# rascsi_din.net
KiCad netlist of a schematic drawn in EAGLE
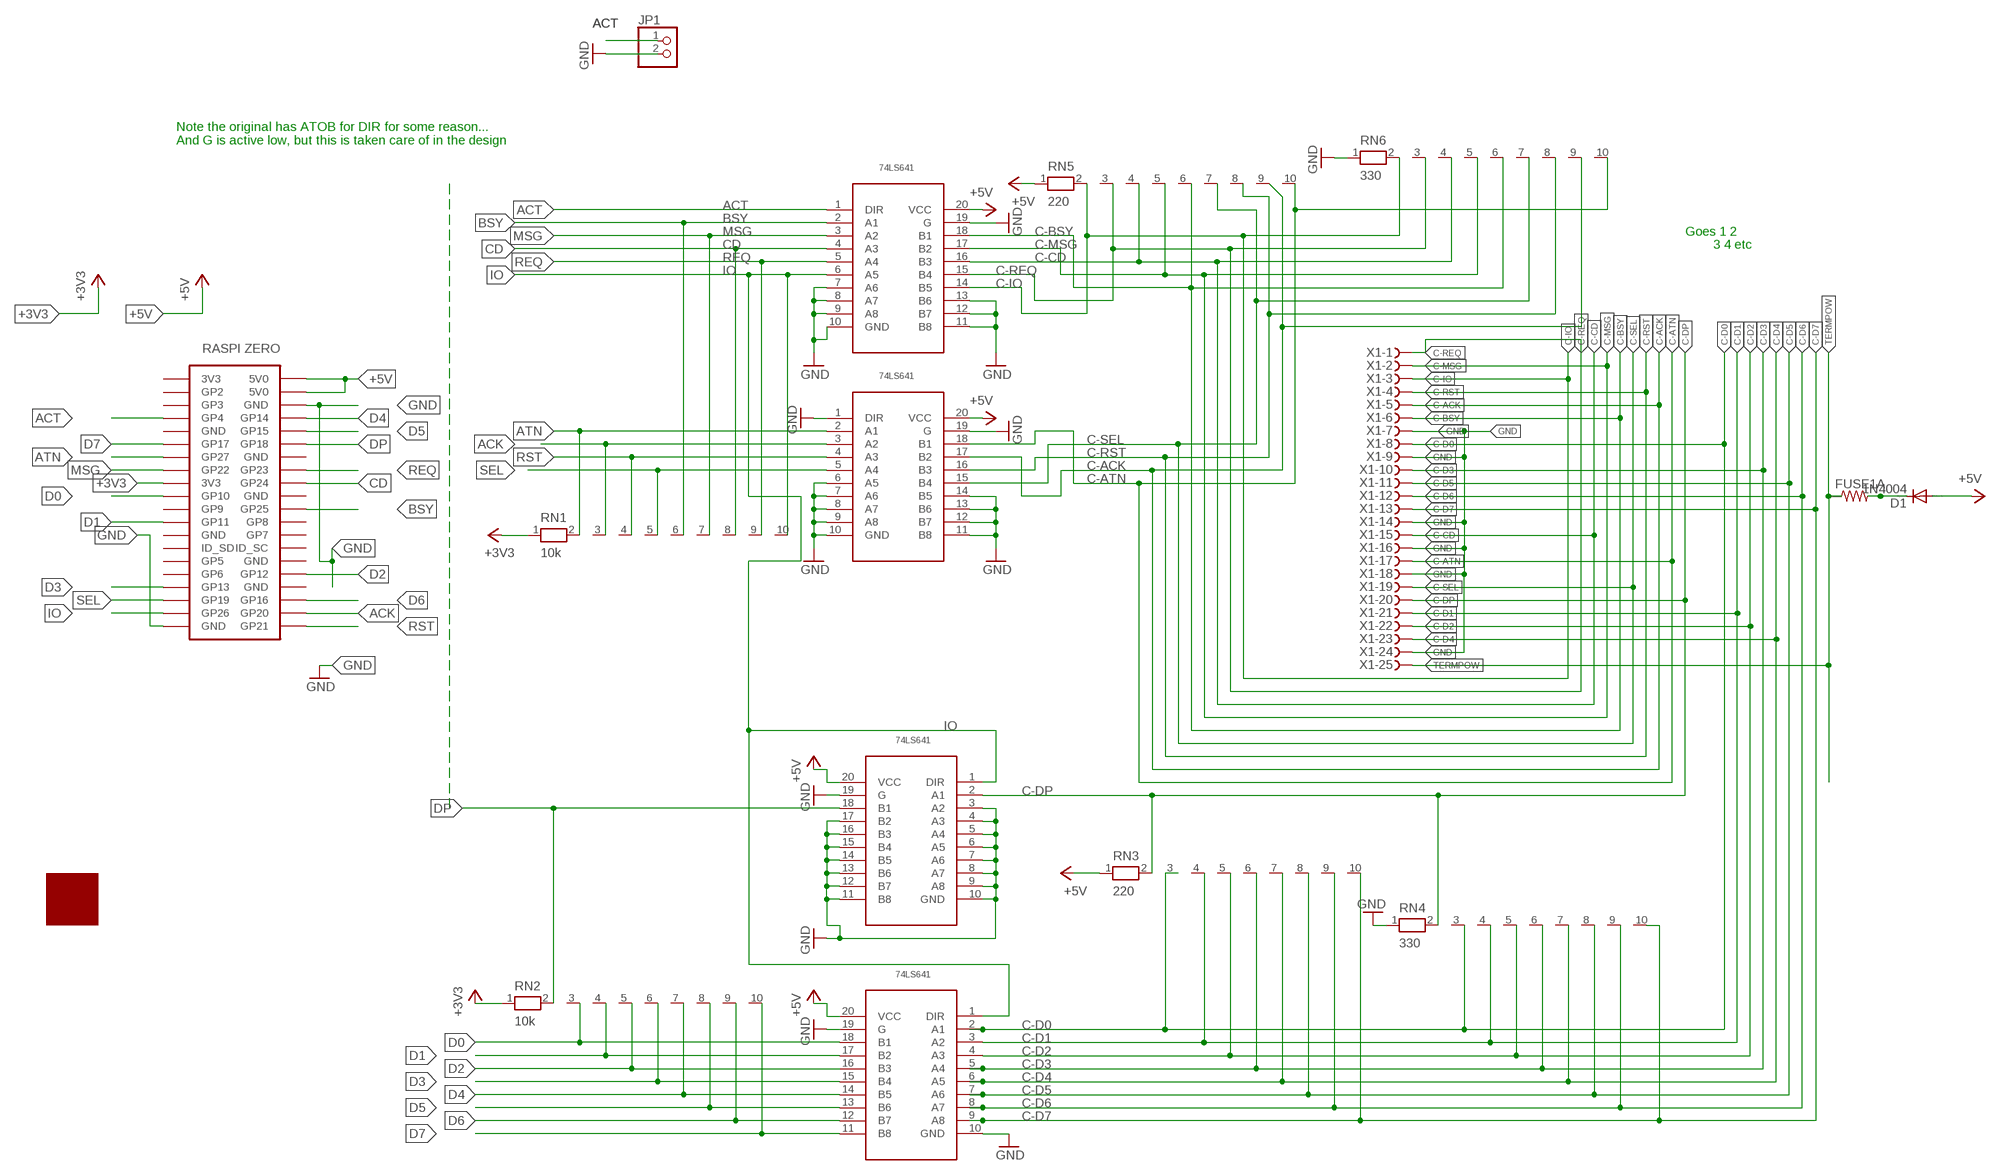
[diagram p0: schematic, sheet 1]

(export (version "E")
  (design (tool "Eeschema 10.0.6"))
  (components
    (comp (ref "D1")
      (value "1N4004")
      (footprint "eagle-import:DO41-10")
      (libsource (lib "eagle-import") (part "1N4004"))
    )
    (comp (ref "FUSE1A")
      (value "R-US_0204/7")
      (footprint "eagle-import:0204_7")
      (libsource (lib "eagle-import") (part "R-US_0204/7"))
    )
    (comp (ref "JP1")
      (value "PINHD-1X2")
      (footprint "eagle-import:1X02")
      (libsource (lib "eagle-import") (part "PINHD-1X2"))
    )
    (comp (ref "RN1")
      (value "10k")
      (footprint "eagle-import:RN-10")
      (libsource (lib "eagle-import") (part "RN09"))
    )
    (comp (ref "RN2")
      (value "10k")
      (footprint "eagle-import:RN-10")
      (libsource (lib "eagle-import") (part "RN09"))
    )
    (comp (ref "RN3")
      (value "220")
      (footprint "eagle-import:RN-10")
      (libsource (lib "eagle-import") (part "RN09"))
    )
    (comp (ref "RN4")
      (value "330")
      (footprint "eagle-import:RN-10")
      (libsource (lib "eagle-import") (part "RN09"))
    )
    (comp (ref "RN5")
      (value "220")
      (footprint "eagle-import:RN-10")
      (libsource (lib "eagle-import") (part "RN09"))
    )
    (comp (ref "RN6")
      (value "330")
      (footprint "eagle-import:RN-10")
      (libsource (lib "eagle-import") (part "RN09"))
    )
    (comp (ref "U$1")
      (value "ZERO")
      (footprint "eagle-import:ZERO")
      (libsource (lib "eagle-import") (part "ZERO"))
    )
    (comp (ref "U$2")
      (value "LOGO")
      (footprint "eagle-import:LOGO")
      (libsource (lib "eagle-import") (part "LOGO"))
    )
    (comp (ref "U11")
      (value "SN74LS641-1SC")
      (footprint "eagle-import:SOIC20S")
      (libsource (lib "eagle-import") (part "SN74LS641-1CS"))
    )
    (comp (ref "U22")
      (value "SN74LS641-1SC")
      (footprint "eagle-import:SOIC20S")
      (libsource (lib "eagle-import") (part "SN74LS641-1CS"))
    )
    (comp (ref "U33")
      (value "SN74LS641-1SC")
      (footprint "eagle-import:SOIC20S")
      (libsource (lib "eagle-import") (part "SN74LS641-1CS"))
    )
    (comp (ref "U44")
      (value "SN74LS641-1SC")
      (footprint "eagle-import:SOIC20S")
      (libsource (lib "eagle-import") (part "SN74LS641-1CS"))
    )
    (comp (ref "X1")
      (value "F25HPS")
      (footprint "eagle-import:F25HP")
      (libsource (lib "eagle-import") (part "F25?SHP"))
    )
  )
  (nets
    (net (code "1") (name "+3V3") (class "Default")
      (node (ref "RN1") (pin "1") (pinfunction "1_1") (pintype "passive"))
      (node (ref "RN2") (pin "1") (pinfunction "1_1") (pintype "passive"))
      (node (ref "U$1") (pin "17") (pinfunction "3V3_17") (pintype "bidirectional"))
    )
    (net (code "2") (name "+5V") (class "Default")
      (node (ref "D1") (pin "A") (pinfunction "A_A") (pintype "passive"))
      (node (ref "RN3") (pin "1") (pinfunction "1_1") (pintype "passive"))
      (node (ref "RN5") (pin "1") (pinfunction "1_1") (pintype "passive"))
      (node (ref "U$1") (pin "2") (pinfunction "5V0_2") (pintype "bidirectional"))
      (node (ref "U$1") (pin "4") (pinfunction "5V0_4") (pintype "bidirectional"))
      (node (ref "U11") (pin "20") (pinfunction "VCC_20") (pintype "power_in"))
      (node (ref "U22") (pin "20") (pinfunction "VCC_20") (pintype "power_in"))
      (node (ref "U33") (pin "20") (pinfunction "VCC_20") (pintype "power_in"))
      (node (ref "U44") (pin "20") (pinfunction "VCC_20") (pintype "power_in"))
    )
    (net (code "3") (name "ACK") (class "Default")
      (node (ref "RN1") (pin "3") (pinfunction "3_3") (pintype "passive"))
      (node (ref "U$1") (pin "38") (pinfunction "GP20_38") (pintype "bidirectional"))
      (node (ref "U22") (pin "3") (pinfunction "A2_3") (pintype "bidirectional"))
    )
    (net (code "4") (name "ACT") (class "Default")
      (node (ref "JP1") (pin "1") (pinfunction "1_1") (pintype "passive"))
      (node (ref "U$1") (pin "7") (pinfunction "GP4_7") (pintype "bidirectional"))
      (node (ref "U11") (pin "1") (pinfunction "DIR_1") (pintype "bidirectional"))
    )
    (net (code "5") (name "ATN") (class "Default")
      (node (ref "RN1") (pin "2") (pinfunction "2_2") (pintype "passive"))
      (node (ref "U$1") (pin "13") (pinfunction "GP27_13") (pintype "bidirectional"))
      (node (ref "U22") (pin "2") (pinfunction "A1_2") (pintype "bidirectional"))
    )
    (net (code "6") (name "BSY") (class "Default")
      (node (ref "RN1") (pin "6") (pinfunction "6_6") (pintype "passive"))
      (node (ref "U$1") (pin "22") (pinfunction "GP25_22") (pintype "bidirectional"))
      (node (ref "U11") (pin "2") (pinfunction "A1_2") (pintype "bidirectional"))
    )
    (net (code "7") (name "C-ACK") (class "Default")
      (node (ref "RN5") (pin "9") (pinfunction "9_9") (pintype "passive"))
      (node (ref "RN6") (pin "9") (pinfunction "9_9") (pintype "passive"))
      (node (ref "U22") (pin "17") (pinfunction "B2_17") (pintype "bidirectional"))
      (node (ref "X1") (pin "5") (pinfunction "F_5") (pintype "passive"))
    )
    (net (code "8") (name "C-ATN") (class "Default")
      (node (ref "RN5") (pin "10") (pinfunction "10_10") (pintype "passive"))
      (node (ref "RN6") (pin "10") (pinfunction "10_10") (pintype "passive"))
      (node (ref "U22") (pin "18") (pinfunction "B1_18") (pintype "bidirectional"))
      (node (ref "X1") (pin "17") (pinfunction "F_17") (pintype "passive"))
    )
    (net (code "9") (name "C-BSY") (class "Default")
      (node (ref "RN5") (pin "6") (pinfunction "6_6") (pintype "passive"))
      (node (ref "RN6") (pin "6") (pinfunction "6_6") (pintype "passive"))
      (node (ref "U11") (pin "18") (pinfunction "B1_18") (pintype "bidirectional"))
      (node (ref "X1") (pin "6") (pinfunction "F_6") (pintype "passive"))
    )
    (net (code "10") (name "C-CD") (class "Default")
      (node (ref "RN5") (pin "4") (pinfunction "4_4") (pintype "passive"))
      (node (ref "RN6") (pin "4") (pinfunction "4_4") (pintype "passive"))
      (node (ref "U11") (pin "16") (pinfunction "B3_16") (pintype "bidirectional"))
      (node (ref "X1") (pin "15") (pinfunction "F_15") (pintype "passive"))
    )
    (net (code "11") (name "C-D0") (class "Default")
      (node (ref "RN3") (pin "3") (pinfunction "3_3") (pintype "passive"))
      (node (ref "RN4") (pin "3") (pinfunction "3_3") (pintype "passive"))
      (node (ref "U44") (pin "2") (pinfunction "A1_2") (pintype "bidirectional"))
      (node (ref "X1") (pin "8") (pinfunction "F_8") (pintype "passive"))
    )
    (net (code "12") (name "C-D1") (class "Default")
      (node (ref "RN3") (pin "4") (pinfunction "4_4") (pintype "passive"))
      (node (ref "RN4") (pin "4") (pinfunction "4_4") (pintype "passive"))
      (node (ref "U44") (pin "3") (pinfunction "A2_3") (pintype "bidirectional"))
      (node (ref "X1") (pin "21") (pinfunction "F_21") (pintype "passive"))
    )
    (net (code "13") (name "C-D2") (class "Default")
      (node (ref "RN3") (pin "5") (pinfunction "5_5") (pintype "passive"))
      (node (ref "RN4") (pin "5") (pinfunction "5_5") (pintype "passive"))
      (node (ref "U44") (pin "4") (pinfunction "A3_4") (pintype "bidirectional"))
      (node (ref "X1") (pin "22") (pinfunction "F_22") (pintype "passive"))
    )
    (net (code "14") (name "C-D3") (class "Default")
      (node (ref "RN3") (pin "6") (pinfunction "6_6") (pintype "passive"))
      (node (ref "RN4") (pin "6") (pinfunction "6_6") (pintype "passive"))
      (node (ref "U44") (pin "5") (pinfunction "A4_5") (pintype "bidirectional"))
      (node (ref "X1") (pin "10") (pinfunction "F_10") (pintype "passive"))
    )
    (net (code "15") (name "C-D4") (class "Default")
      (node (ref "RN3") (pin "7") (pinfunction "7_7") (pintype "passive"))
      (node (ref "RN4") (pin "7") (pinfunction "7_7") (pintype "passive"))
      (node (ref "U44") (pin "6") (pinfunction "A5_6") (pintype "bidirectional"))
      (node (ref "X1") (pin "23") (pinfunction "F_23") (pintype "passive"))
    )
    (net (code "16") (name "C-D5") (class "Default")
      (node (ref "RN3") (pin "8") (pinfunction "8_8") (pintype "passive"))
      (node (ref "RN4") (pin "8") (pinfunction "8_8") (pintype "passive"))
      (node (ref "U44") (pin "7") (pinfunction "A6_7") (pintype "bidirectional"))
      (node (ref "X1") (pin "11") (pinfunction "F_11") (pintype "passive"))
    )
    (net (code "17") (name "C-D6") (class "Default")
      (node (ref "RN3") (pin "9") (pinfunction "9_9") (pintype "passive"))
      (node (ref "RN4") (pin "9") (pinfunction "9_9") (pintype "passive"))
      (node (ref "U44") (pin "8") (pinfunction "A7_8") (pintype "bidirectional"))
      (node (ref "X1") (pin "12") (pinfunction "F_12") (pintype "passive"))
    )
    (net (code "18") (name "C-D7") (class "Default")
      (node (ref "RN3") (pin "10") (pinfunction "10_10") (pintype "passive"))
      (node (ref "RN4") (pin "10") (pinfunction "10_10") (pintype "passive"))
      (node (ref "U44") (pin "9") (pinfunction "A8_9") (pintype "bidirectional"))
      (node (ref "X1") (pin "13") (pinfunction "F_13") (pintype "passive"))
    )
    (net (code "19") (name "C-DP") (class "Default")
      (node (ref "RN3") (pin "2") (pinfunction "2_2") (pintype "passive"))
      (node (ref "RN4") (pin "2") (pinfunction "2_2") (pintype "passive"))
      (node (ref "U33") (pin "2") (pinfunction "A1_2") (pintype "bidirectional"))
      (node (ref "X1") (pin "20") (pinfunction "F_20") (pintype "passive"))
    )
    (net (code "20") (name "C-IO") (class "Default")
      (node (ref "RN5") (pin "2") (pinfunction "2_2") (pintype "passive"))
      (node (ref "RN6") (pin "2") (pinfunction "2_2") (pintype "passive"))
      (node (ref "U11") (pin "14") (pinfunction "B5_14") (pintype "bidirectional"))
      (node (ref "X1") (pin "3") (pinfunction "F_3") (pintype "passive"))
    )
    (net (code "21") (name "C-MSG") (class "Default")
      (node (ref "RN5") (pin "5") (pinfunction "5_5") (pintype "passive"))
      (node (ref "RN6") (pin "5") (pinfunction "5_5") (pintype "passive"))
      (node (ref "U11") (pin "17") (pinfunction "B2_17") (pintype "bidirectional"))
      (node (ref "X1") (pin "2") (pinfunction "F_2") (pintype "passive"))
    )
    (net (code "22") (name "C-REQ") (class "Default")
      (node (ref "RN5") (pin "3") (pinfunction "3_3") (pintype "passive"))
      (node (ref "RN6") (pin "3") (pinfunction "3_3") (pintype "passive"))
      (node (ref "U11") (pin "15") (pinfunction "B4_15") (pintype "bidirectional"))
      (node (ref "X1") (pin "1") (pinfunction "F_1") (pintype "passive"))
    )
    (net (code "23") (name "C-RST") (class "Default")
      (node (ref "RN5") (pin "8") (pinfunction "8_8") (pintype "passive"))
      (node (ref "RN6") (pin "8") (pinfunction "8_8") (pintype "passive"))
      (node (ref "U22") (pin "16") (pinfunction "B3_16") (pintype "bidirectional"))
      (node (ref "X1") (pin "4") (pinfunction "F_4") (pintype "passive"))
    )
    (net (code "24") (name "C-SEL") (class "Default")
      (node (ref "RN5") (pin "7") (pinfunction "7_7") (pintype "passive"))
      (node (ref "RN6") (pin "7") (pinfunction "7_7") (pintype "passive"))
      (node (ref "U22") (pin "15") (pinfunction "B4_15") (pintype "bidirectional"))
      (node (ref "X1") (pin "19") (pinfunction "F_19") (pintype "passive"))
    )
    (net (code "25") (name "CD") (class "Default")
      (node (ref "RN1") (pin "8") (pinfunction "8_8") (pintype "passive"))
      (node (ref "U$1") (pin "18") (pinfunction "GP24_18") (pintype "bidirectional"))
      (node (ref "U11") (pin "4") (pinfunction "A3_4") (pintype "bidirectional"))
    )
    (net (code "26") (name "D0") (class "Default")
      (node (ref "RN2") (pin "3") (pinfunction "3_3") (pintype "passive"))
      (node (ref "U$1") (pin "19") (pinfunction "GP10_19") (pintype "bidirectional"))
      (node (ref "U44") (pin "18") (pinfunction "B1_18") (pintype "bidirectional"))
    )
    (net (code "27") (name "D1") (class "Default")
      (node (ref "RN2") (pin "4") (pinfunction "4_4") (pintype "passive"))
      (node (ref "U$1") (pin "23") (pinfunction "GP11_23") (pintype "bidirectional"))
      (node (ref "U44") (pin "17") (pinfunction "B2_17") (pintype "bidirectional"))
    )
    (net (code "28") (name "D2") (class "Default")
      (node (ref "RN2") (pin "5") (pinfunction "5_5") (pintype "passive"))
      (node (ref "U$1") (pin "32") (pinfunction "GP12_32") (pintype "bidirectional"))
      (node (ref "U44") (pin "16") (pinfunction "B3_16") (pintype "bidirectional"))
    )
    (net (code "29") (name "D3") (class "Default")
      (node (ref "RN2") (pin "6") (pinfunction "6_6") (pintype "passive"))
      (node (ref "U$1") (pin "33") (pinfunction "GP13_33") (pintype "bidirectional"))
      (node (ref "U44") (pin "15") (pinfunction "B4_15") (pintype "bidirectional"))
    )
    (net (code "30") (name "D4") (class "Default")
      (node (ref "RN2") (pin "7") (pinfunction "7_7") (pintype "passive"))
      (node (ref "U$1") (pin "8") (pinfunction "GP14_8") (pintype "bidirectional"))
      (node (ref "U44") (pin "14") (pinfunction "B5_14") (pintype "bidirectional"))
    )
    (net (code "31") (name "D5") (class "Default")
      (node (ref "RN2") (pin "8") (pinfunction "8_8") (pintype "passive"))
      (node (ref "U$1") (pin "10") (pinfunction "GP15_10") (pintype "bidirectional"))
      (node (ref "U44") (pin "13") (pinfunction "B6_13") (pintype "bidirectional"))
    )
    (net (code "32") (name "D6") (class "Default")
      (node (ref "RN2") (pin "9") (pinfunction "9_9") (pintype "passive"))
      (node (ref "U$1") (pin "36") (pinfunction "GP16_36") (pintype "bidirectional"))
      (node (ref "U44") (pin "12") (pinfunction "B7_12") (pintype "bidirectional"))
    )
    (net (code "33") (name "D7") (class "Default")
      (node (ref "RN2") (pin "10") (pinfunction "10_10") (pintype "passive"))
      (node (ref "U$1") (pin "11") (pinfunction "GP17_11") (pintype "bidirectional"))
      (node (ref "U44") (pin "11") (pinfunction "B8_11") (pintype "bidirectional"))
    )
    (net (code "34") (name "DP") (class "Default")
      (node (ref "RN2") (pin "2") (pinfunction "2_2") (pintype "passive"))
      (node (ref "U$1") (pin "12") (pinfunction "GP18_12") (pintype "bidirectional"))
      (node (ref "U33") (pin "18") (pinfunction "B1_18") (pintype "bidirectional"))
    )
    (net (code "35") (name "GND") (class "Default")
      (node (ref "JP1") (pin "2") (pinfunction "2_2") (pintype "passive"))
      (node (ref "RN4") (pin "1") (pinfunction "1_1") (pintype "passive"))
      (node (ref "RN6") (pin "1") (pinfunction "1_1") (pintype "passive"))
      (node (ref "U$1") (pin "39") (pinfunction "GND_39") (pintype "bidirectional"))
      (node (ref "U$1") (pin "6") (pinfunction "GND_6") (pintype "bidirectional"))
      (node (ref "U11") (pin "10") (pinfunction "GND_10") (pintype "power_in"))
      (node (ref "U11") (pin "11") (pinfunction "B8_11") (pintype "bidirectional"))
      (node (ref "U11") (pin "12") (pinfunction "B7_12") (pintype "bidirectional"))
      (node (ref "U11") (pin "13") (pinfunction "B6_13") (pintype "bidirectional"))
      (node (ref "U11") (pin "19") (pinfunction "G_19") (pintype "bidirectional"))
      (node (ref "U11") (pin "7") (pinfunction "A6_7") (pintype "bidirectional"))
      (node (ref "U11") (pin "8") (pinfunction "A7_8") (pintype "bidirectional"))
      (node (ref "U11") (pin "9") (pinfunction "A8_9") (pintype "bidirectional"))
      (node (ref "U22") (pin "1") (pinfunction "DIR_1") (pintype "bidirectional"))
      (node (ref "U22") (pin "10") (pinfunction "GND_10") (pintype "power_in"))
      (node (ref "U22") (pin "11") (pinfunction "B8_11") (pintype "bidirectional"))
      (node (ref "U22") (pin "12") (pinfunction "B7_12") (pintype "bidirectional"))
      (node (ref "U22") (pin "13") (pinfunction "B6_13") (pintype "bidirectional"))
      (node (ref "U22") (pin "14") (pinfunction "B5_14") (pintype "bidirectional"))
      (node (ref "U22") (pin "19") (pinfunction "G_19") (pintype "bidirectional"))
      (node (ref "U22") (pin "6") (pinfunction "A5_6") (pintype "bidirectional"))
      (node (ref "U22") (pin "7") (pinfunction "A6_7") (pintype "bidirectional"))
      (node (ref "U22") (pin "8") (pinfunction "A7_8") (pintype "bidirectional"))
      (node (ref "U22") (pin "9") (pinfunction "A8_9") (pintype "bidirectional"))
      (node (ref "U33") (pin "10") (pinfunction "GND_10") (pintype "power_in"))
      (node (ref "U33") (pin "11") (pinfunction "B8_11") (pintype "bidirectional"))
      (node (ref "U33") (pin "12") (pinfunction "B7_12") (pintype "bidirectional"))
      (node (ref "U33") (pin "13") (pinfunction "B6_13") (pintype "bidirectional"))
      (node (ref "U33") (pin "14") (pinfunction "B5_14") (pintype "bidirectional"))
      (node (ref "U33") (pin "15") (pinfunction "B4_15") (pintype "bidirectional"))
      (node (ref "U33") (pin "16") (pinfunction "B3_16") (pintype "bidirectional"))
      (node (ref "U33") (pin "17") (pinfunction "B2_17") (pintype "bidirectional"))
      (node (ref "U33") (pin "19") (pinfunction "G_19") (pintype "bidirectional"))
      (node (ref "U33") (pin "3") (pinfunction "A2_3") (pintype "bidirectional"))
      (node (ref "U33") (pin "4") (pinfunction "A3_4") (pintype "bidirectional"))
      (node (ref "U33") (pin "5") (pinfunction "A4_5") (pintype "bidirectional"))
      (node (ref "U33") (pin "6") (pinfunction "A5_6") (pintype "bidirectional"))
      (node (ref "U33") (pin "7") (pinfunction "A6_7") (pintype "bidirectional"))
      (node (ref "U33") (pin "8") (pinfunction "A7_8") (pintype "bidirectional"))
      (node (ref "U33") (pin "9") (pinfunction "A8_9") (pintype "bidirectional"))
      (node (ref "U44") (pin "10") (pinfunction "GND_10") (pintype "power_in"))
      (node (ref "U44") (pin "19") (pinfunction "G_19") (pintype "bidirectional"))
      (node (ref "X1") (pin "14") (pinfunction "F_14") (pintype "passive"))
      (node (ref "X1") (pin "16") (pinfunction "F_16") (pintype "passive"))
      (node (ref "X1") (pin "18") (pinfunction "F_18") (pintype "passive"))
      (node (ref "X1") (pin "24") (pinfunction "F_24") (pintype "passive"))
      (node (ref "X1") (pin "7") (pinfunction "F_7") (pintype "passive"))
      (node (ref "X1") (pin "9") (pinfunction "F_9") (pintype "passive"))
    )
    (net (code "36") (name "IO") (class "Default")
      (node (ref "RN1") (pin "10") (pinfunction "10_10") (pintype "passive"))
      (node (ref "U$1") (pin "37") (pinfunction "GP26_37") (pintype "bidirectional"))
      (node (ref "U11") (pin "6") (pinfunction "A5_6") (pintype "bidirectional"))
      (node (ref "U33") (pin "1") (pinfunction "DIR_1") (pintype "bidirectional"))
      (node (ref "U44") (pin "1") (pinfunction "DIR_1") (pintype "bidirectional"))
    )
    (net (code "37") (name "MSG") (class "Default")
      (node (ref "RN1") (pin "7") (pinfunction "7_7") (pintype "passive"))
      (node (ref "U$1") (pin "15") (pinfunction "GP22_15") (pintype "bidirectional"))
      (node (ref "U11") (pin "3") (pinfunction "A2_3") (pintype "bidirectional"))
    )
    (net (code "38") (name "Net-(D1-PadC)") (class "Default")
      (node (ref "D1") (pin "C") (pinfunction "C_C") (pintype "passive"))
      (node (ref "FUSE1A") (pin "2") (pinfunction "2_2") (pintype "passive"))
    )
    (net (code "39") (name "REQ") (class "Default")
      (node (ref "RN1") (pin "9") (pinfunction "9_9") (pintype "passive"))
      (node (ref "U$1") (pin "16") (pinfunction "GP23_16") (pintype "bidirectional"))
      (node (ref "U11") (pin "5") (pinfunction "A4_5") (pintype "bidirectional"))
    )
    (net (code "40") (name "RST") (class "Default")
      (node (ref "RN1") (pin "4") (pinfunction "4_4") (pintype "passive"))
      (node (ref "U$1") (pin "40") (pinfunction "GP21_40") (pintype "bidirectional"))
      (node (ref "U22") (pin "4") (pinfunction "A3_4") (pintype "bidirectional"))
    )
    (net (code "41") (name "SEL") (class "Default")
      (node (ref "RN1") (pin "5") (pinfunction "5_5") (pintype "passive"))
      (node (ref "U$1") (pin "35") (pinfunction "GP19_35") (pintype "bidirectional"))
      (node (ref "U22") (pin "5") (pinfunction "A4_5") (pintype "bidirectional"))
    )
    (net (code "42") (name "TERMPOW") (class "Default")
      (node (ref "FUSE1A") (pin "1") (pinfunction "1_1") (pintype "passive"))
      (node (ref "X1") (pin "25") (pinfunction "F_25") (pintype "passive"))
    )
    (net (code "43") (name "unconnected-(U$1-3V3-Pad1)") (class "Default")
      (node (ref "U$1") (pin "1") (pinfunction "3V3_1") (pintype "bidirectional"))
    )
    (net (code "44") (name "unconnected-(U$1-GND-Pad9)") (class "Default")
      (node (ref "U$1") (pin "9") (pinfunction "GND_9") (pintype "bidirectional"))
    )
    (net (code "45") (name "unconnected-(U$1-GND-Pad14)") (class "Default")
      (node (ref "U$1") (pin "14") (pinfunction "GND_14") (pintype "bidirectional"))
    )
    (net (code "46") (name "unconnected-(U$1-GND-Pad20)") (class "Default")
      (node (ref "U$1") (pin "20") (pinfunction "GND_20") (pintype "bidirectional"))
    )
    (net (code "47") (name "unconnected-(U$1-GND-Pad25)") (class "Default")
      (node (ref "U$1") (pin "25") (pinfunction "GND_25") (pintype "bidirectional"))
    )
    (net (code "48") (name "unconnected-(U$1-GND-Pad30)") (class "Default")
      (node (ref "U$1") (pin "30") (pinfunction "GND_30") (pintype "bidirectional"))
    )
    (net (code "49") (name "unconnected-(U$1-GND-Pad34)") (class "Default")
      (node (ref "U$1") (pin "34") (pinfunction "GND_34") (pintype "bidirectional"))
    )
    (net (code "50") (name "unconnected-(U$1-GP2-Pad3)") (class "Default")
      (node (ref "U$1") (pin "3") (pinfunction "GP2_3") (pintype "bidirectional"))
    )
    (net (code "51") (name "unconnected-(U$1-GP3-Pad5)") (class "Default")
      (node (ref "U$1") (pin "5") (pinfunction "GP3_5") (pintype "bidirectional"))
    )
    (net (code "52") (name "unconnected-(U$1-GP5-Pad29)") (class "Default")
      (node (ref "U$1") (pin "29") (pinfunction "GP5_29") (pintype "bidirectional"))
    )
    (net (code "53") (name "unconnected-(U$1-GP6-Pad31)") (class "Default")
      (node (ref "U$1") (pin "31") (pinfunction "GP6_31") (pintype "bidirectional"))
    )
    (net (code "54") (name "unconnected-(U$1-GP7-Pad26)") (class "Default")
      (node (ref "U$1") (pin "26") (pinfunction "GP7_26") (pintype "bidirectional"))
    )
    (net (code "55") (name "unconnected-(U$1-GP8-Pad24)") (class "Default")
      (node (ref "U$1") (pin "24") (pinfunction "GP8_24") (pintype "bidirectional"))
    )
    (net (code "56") (name "unconnected-(U$1-GP9-Pad21)") (class "Default")
      (node (ref "U$1") (pin "21") (pinfunction "GP9_21") (pintype "bidirectional"))
    )
    (net (code "57") (name "unconnected-(U$1-ID_SC-Pad28)") (class "Default")
      (node (ref "U$1") (pin "28") (pinfunction "ID_SC_28") (pintype "bidirectional"))
    )
    (net (code "58") (name "unconnected-(U$1-ID_SD-Pad27)") (class "Default")
      (node (ref "U$1") (pin "27") (pinfunction "ID_SD_27") (pintype "bidirectional"))
    )
  )
)
